# Gamepad_Seesaw_QT_rev_A.net
KiCad netlist of a schematic drawn in EAGLE
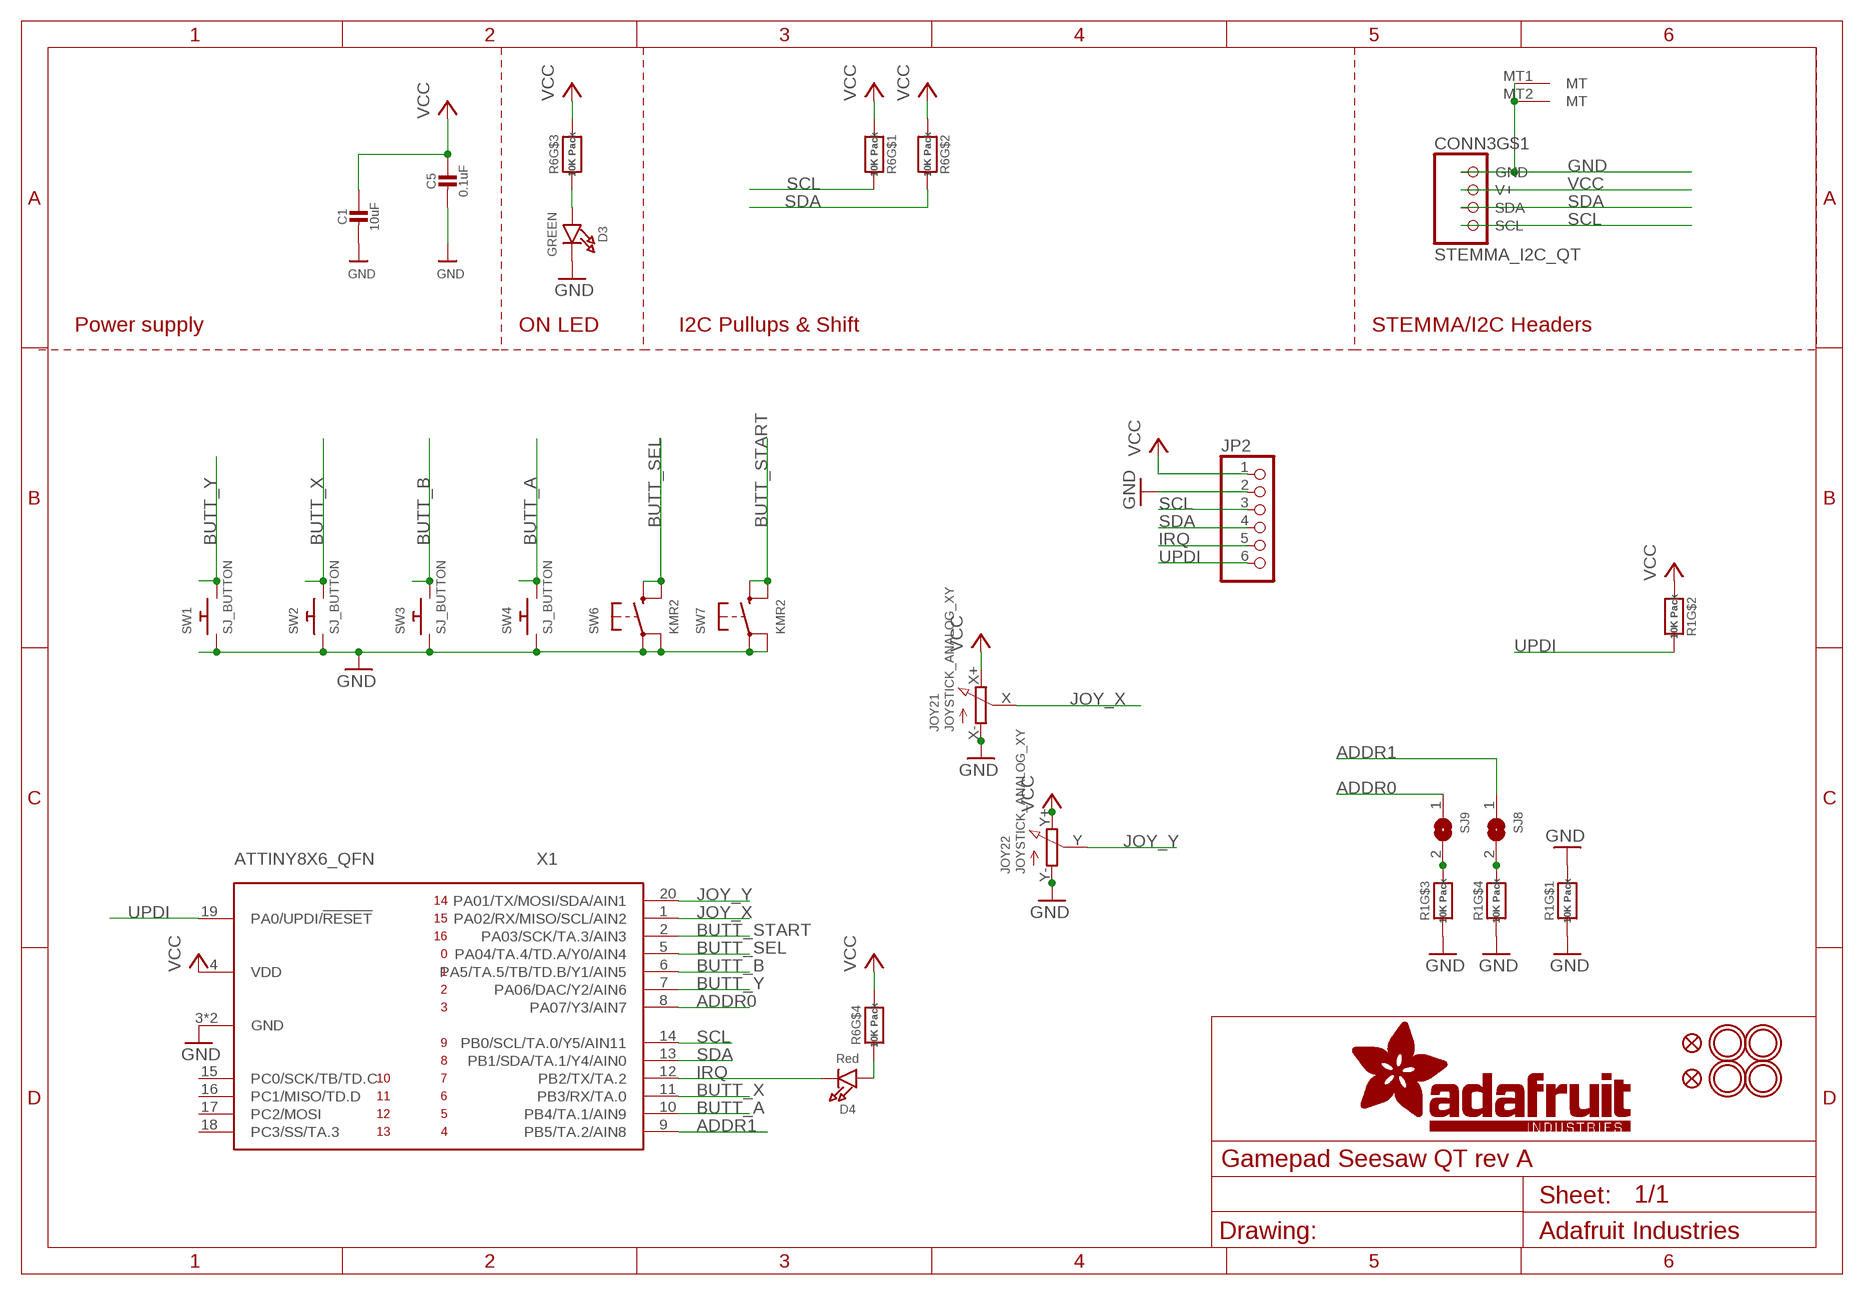
[diagram p0: schematic, sheet 1]

(export (version "E")
  (design (tool "Eeschema 10.0.6"))
  (components
    (comp (ref "C1")
      (value "10uF")
      (footprint "eagle-import:0805-NO")
      (libsource (lib "eagle-import") (part "CAP_CERAMIC0805-NOOUTLINE"))
    )
    (comp (ref "C5")
      (value "0.1uF")
      (footprint "eagle-import:0603-NO")
      (libsource (lib "eagle-import") (part "CAP_CERAMIC0603_NO"))
    )
    (comp (ref "CONN3")
      (value "STEMMA_I2C_QT")
      (footprint "eagle-import:JST_SH4")
      (libsource (lib "eagle-import") (part "STEMMA_I2C_QT"))
    )
    (comp (ref "D3")
      (value "GREEN")
      (footprint "eagle-import:CHIPLED_0603_NOOUTLINE")
      (libsource (lib "eagle-import") (part "LED0603_NOOUTLINE"))
    )
    (comp (ref "D4")
      (value "Red")
      (footprint "eagle-import:CHIPLED_0603_NOOUTLINE")
      (libsource (lib "eagle-import") (part "LED0603_NOOUTLINE"))
    )
    (comp (ref "FID1")
      (value "FIDUCIAL_1MM")
      (footprint "eagle-import:FIDUCIAL_1MM")
      (libsource (lib "eagle-import") (part "FIDUCIAL_1MM"))
    )
    (comp (ref "FID2")
      (value "FIDUCIAL_1MM")
      (footprint "eagle-import:FIDUCIAL_1MM")
      (libsource (lib "eagle-import") (part "FIDUCIAL_1MM"))
    )
    (comp (ref "JOY2")
      (value "JOYSTICK_ANALOG_XY")
      (footprint "eagle-import:JOYSTICK_ANALOG_MINITHM")
      (libsource (lib "eagle-import") (part "JOYSTICK_ANALOG_XY"))
    )
    (comp (ref "JP2")
      (value "HEADER-1X6ROUND")
      (footprint "eagle-import:1X06_ROUND")
      (libsource (lib "eagle-import") (part "HEADER-1X6ROUND"))
    )
    (comp (ref "R1")
      (value "10K Pack")
      (footprint "eagle-import:RESPACK_4X0603")
      (libsource (lib "eagle-import") (part "RESISTOR_4PACK"))
    )
    (comp (ref "R6")
      (value "10K Pack")
      (footprint "eagle-import:RESPACK_4X0603")
      (libsource (lib "eagle-import") (part "RESISTOR_4PACK"))
    )
    (comp (ref "SJ8")
      (value "SOLDERJUMPERCLOSED")
      (footprint "eagle-import:SOLDERJUMPER_CLOSEDWIRE")
      (libsource (lib "eagle-import") (part "SOLDERJUMPERCLOSED"))
    )
    (comp (ref "SJ9")
      (value "SOLDERJUMPERCLOSED")
      (footprint "eagle-import:SOLDERJUMPER_CLOSEDWIRE")
      (libsource (lib "eagle-import") (part "SOLDERJUMPERCLOSED"))
    )
    (comp (ref "SW1")
      (value "SJ_BUTTON")
      (footprint "eagle-import:PUSHBUTTON_SMD_SJ")
      (libsource (lib "eagle-import") (part "SWITCH_PUSHBUTTONSOFTTOUCHSMD_SJ"))
    )
    (comp (ref "SW2")
      (value "SJ_BUTTON")
      (footprint "eagle-import:PUSHBUTTON_SMD_SJ")
      (libsource (lib "eagle-import") (part "SWITCH_PUSHBUTTONSOFTTOUCHSMD_SJ"))
    )
    (comp (ref "SW3")
      (value "SJ_BUTTON")
      (footprint "eagle-import:PUSHBUTTON_SMD_SJ")
      (libsource (lib "eagle-import") (part "SWITCH_PUSHBUTTONSOFTTOUCHSMD_SJ"))
    )
    (comp (ref "SW4")
      (value "SJ_BUTTON")
      (footprint "eagle-import:PUSHBUTTON_SMD_SJ")
      (libsource (lib "eagle-import") (part "SWITCH_PUSHBUTTONSOFTTOUCHSMD_SJ"))
    )
    (comp (ref "SW6")
      (value "KMR2")
      (footprint "eagle-import:BTN_RKB2_4.6X2.8")
      (libsource (lib "eagle-import") (part "SWITCH_TACT_SMT_RKB2"))
    )
    (comp (ref "SW7")
      (value "KMR2")
      (footprint "eagle-import:BTN_RKB2_4.6X2.8")
      (libsource (lib "eagle-import") (part "SWITCH_TACT_SMT_RKB2"))
    )
    (comp (ref "U$1")
      (value "MOUNTINGHOLE2.5")
      (footprint "eagle-import:MOUNTINGHOLE_2.5_PLATED")
      (libsource (lib "eagle-import") (part "MOUNTINGHOLE2.5"))
    )
    (comp (ref "U$2")
      (value "MOUNTINGHOLE2.5")
      (footprint "eagle-import:MOUNTINGHOLE_2.5_PLATED")
      (libsource (lib "eagle-import") (part "MOUNTINGHOLE2.5"))
    )
    (comp (ref "U$3")
      (value "MOUNTINGHOLE2.5")
      (footprint "eagle-import:MOUNTINGHOLE_2.5_PLATED")
      (libsource (lib "eagle-import") (part "MOUNTINGHOLE2.5"))
    )
    (comp (ref "U$4")
      (value "MOUNTINGHOLE2.5")
      (footprint "eagle-import:MOUNTINGHOLE_2.5_PLATED")
      (libsource (lib "eagle-import") (part "MOUNTINGHOLE2.5"))
    )
    (comp (ref "X1")
      (value "ATTINY8X6_QFN")
      (footprint "eagle-import:QFN20_3MM")
      (libsource (lib "eagle-import") (part "ATTINY8X6_QFN"))
    )
  )
  (nets
    (net (code "1") (name "/ADDR0") (class "Default")
      (node (ref "SJ9") (pin "1") (pinfunction "1_1") (pintype "passive"))
      (node (ref "X1") (pin "8") (pinfunction "PA07/Y3/AIN7_8") (pintype "bidirectional"))
    )
    (net (code "2") (name "/ADDR1") (class "Default")
      (node (ref "SJ8") (pin "1") (pinfunction "1_1") (pintype "passive"))
      (node (ref "X1") (pin "9") (pinfunction "PB5/TA.2/AIN8_9") (pintype "bidirectional"))
    )
    (net (code "3") (name "/BUTT_A") (class "Default")
      (node (ref "SW4") (pin "P$2") (pinfunction "P$2_P$2") (pintype "passive"))
      (node (ref "X1") (pin "10") (pinfunction "PB4/TA.1/AIN9_10") (pintype "bidirectional"))
    )
    (net (code "4") (name "/BUTT_B") (class "Default")
      (node (ref "SW3") (pin "P$2") (pinfunction "P$2_P$2") (pintype "passive"))
      (node (ref "X1") (pin "6") (pinfunction "PA5/TA.5/TB/TD.B/Y1/AIN5_6") (pintype "bidirectional"))
    )
    (net (code "5") (name "/BUTT_SEL") (class "Default")
      (node (ref "SW6") (pin "B") (pinfunction "S_B") (pintype "passive"))
      (node (ref "SW6") (pin "B'") (pinfunction "S1_B'") (pintype "passive"))
      (node (ref "X1") (pin "5") (pinfunction "PA04/TA.4/TD.A/Y0/AIN4_5") (pintype "bidirectional"))
    )
    (net (code "6") (name "/BUTT_START") (class "Default")
      (node (ref "SW7") (pin "B") (pinfunction "S_B") (pintype "passive"))
      (node (ref "SW7") (pin "B'") (pinfunction "S1_B'") (pintype "passive"))
      (node (ref "X1") (pin "2") (pinfunction "PA03/SCK/TA.3/AIN3_2") (pintype "bidirectional"))
    )
    (net (code "7") (name "/BUTT_X") (class "Default")
      (node (ref "SW2") (pin "P$2") (pinfunction "P$2_P$2") (pintype "passive"))
      (node (ref "X1") (pin "11") (pinfunction "PB3/RX/TA.0_11") (pintype "bidirectional"))
    )
    (net (code "8") (name "/BUTT_Y") (class "Default")
      (node (ref "SW1") (pin "P$2") (pinfunction "P$2_P$2") (pintype "passive"))
      (node (ref "X1") (pin "7") (pinfunction "PA06/DAC/Y2/AIN6_7") (pintype "bidirectional"))
    )
    (net (code "9") (name "/IRQ") (class "Default")
      (node (ref "D4") (pin "C") (pinfunction "C_C") (pintype "passive"))
      (node (ref "JP2") (pin "5") (pinfunction "5_5") (pintype "passive"))
      (node (ref "X1") (pin "12") (pinfunction "PB2/TX/TA.2_12") (pintype "bidirectional"))
    )
    (net (code "10") (name "/JOY_X") (class "Default")
      (node (ref "JOY2") (pin "X") (pinfunction "S_X") (pintype "passive"))
      (node (ref "X1") (pin "1") (pinfunction "PA02/RX/MISO/SCL/AIN2_1") (pintype "bidirectional"))
    )
    (net (code "11") (name "/JOY_Y") (class "Default")
      (node (ref "JOY2") (pin "Y") (pinfunction "S_Y") (pintype "passive"))
      (node (ref "X1") (pin "20") (pinfunction "PA01/TX/MOSI/SDA/AIN1_20") (pintype "bidirectional"))
    )
    (net (code "12") (name "/SCL") (class "Default")
      (node (ref "CONN3") (pin "4") (pinfunction "SCL_4") (pintype "passive"))
      (node (ref "JP2") (pin "3") (pinfunction "3_3") (pintype "passive"))
      (node (ref "R6") (pin "8") (pinfunction "2_8") (pintype "passive"))
      (node (ref "X1") (pin "14") (pinfunction "PB0/SCL/TA.0/Y5/AIN11_14") (pintype "bidirectional"))
    )
    (net (code "13") (name "/SDA") (class "Default")
      (node (ref "CONN3") (pin "3") (pinfunction "SDA_3") (pintype "passive"))
      (node (ref "JP2") (pin "4") (pinfunction "4_4") (pintype "passive"))
      (node (ref "R6") (pin "7") (pinfunction "2_7") (pintype "passive"))
      (node (ref "X1") (pin "13") (pinfunction "PB1/SDA/TA.1/Y4/AIN0_13") (pintype "bidirectional"))
    )
    (net (code "14") (name "/UPDI") (class "Default")
      (node (ref "JP2") (pin "6") (pinfunction "6_6") (pintype "passive"))
      (node (ref "R1") (pin "7") (pinfunction "2_7") (pintype "passive"))
      (node (ref "X1") (pin "19") (pinfunction "PA0/UPDI/~{RESET}_19") (pintype "bidirectional"))
    )
    (net (code "15") (name "GND") (class "Default")
      (node (ref "C1") (pin "2") (pinfunction "2_2") (pintype "passive"))
      (node (ref "C5") (pin "2") (pinfunction "2_2") (pintype "passive"))
      (node (ref "CONN3") (pin "1") (pinfunction "GND_1") (pintype "passive"))
      (node (ref "CONN3") (pin "MT1") (pinfunction "MT_MT1") (pintype "bidirectional"))
      (node (ref "CONN3") (pin "MT2") (pinfunction "MT_MT2") (pintype "bidirectional"))
      (node (ref "D3") (pin "C") (pinfunction "C_C") (pintype "passive"))
      (node (ref "JOY2") (pin "X-") (pinfunction "A_X-") (pintype "passive"))
      (node (ref "JOY2") (pin "Y-") (pinfunction "A_Y-") (pintype "passive"))
      (node (ref "JP2") (pin "2") (pinfunction "2_2") (pintype "passive"))
      (node (ref "R1") (pin "1") (pinfunction "1_1") (pintype "passive"))
      (node (ref "R1") (pin "3") (pinfunction "1_3") (pintype "passive"))
      (node (ref "R1") (pin "4") (pinfunction "1_4") (pintype "passive"))
      (node (ref "R1") (pin "8") (pinfunction "2_8") (pintype "passive"))
      (node (ref "SW1") (pin "P$1") (pinfunction "P$1_P$1") (pintype "passive"))
      (node (ref "SW2") (pin "P$1") (pinfunction "P$1_P$1") (pintype "passive"))
      (node (ref "SW3") (pin "P$1") (pinfunction "P$1_P$1") (pintype "passive"))
      (node (ref "SW4") (pin "P$1") (pinfunction "P$1_P$1") (pintype "passive"))
      (node (ref "SW6") (pin "A") (pinfunction "P_A") (pintype "passive"))
      (node (ref "SW6") (pin "A'") (pinfunction "P1_A'") (pintype "passive"))
      (node (ref "SW7") (pin "A") (pinfunction "P_A") (pintype "passive"))
      (node (ref "SW7") (pin "A'") (pinfunction "P1_A'") (pintype "passive"))
      (node (ref "X1") (pin "3") (pinfunction "GND_3") (pintype "power_in"))
      (node (ref "X1") (pin "PAD") (pinfunction "GND_PAD") (pintype "power_in"))
    )
    (net (code "16") (name "Net-(R1C-2)") (class "Default")
      (node (ref "R1") (pin "6") (pinfunction "2_6") (pintype "passive"))
      (node (ref "SJ9") (pin "2") (pinfunction "2_2") (pintype "passive"))
    )
    (net (code "17") (name "Net-(R1D-2)") (class "Default")
      (node (ref "R1") (pin "5") (pinfunction "2_5") (pintype "passive"))
      (node (ref "SJ8") (pin "2") (pinfunction "2_2") (pintype "passive"))
    )
    (net (code "18") (name "Net-(R6C-1)") (class "Default")
      (node (ref "D3") (pin "A") (pinfunction "A_A") (pintype "passive"))
      (node (ref "R6") (pin "3") (pinfunction "1_3") (pintype "passive"))
    )
    (net (code "19") (name "Net-(R6D-1)") (class "Default")
      (node (ref "D4") (pin "A") (pinfunction "A_A") (pintype "passive"))
      (node (ref "R6") (pin "4") (pinfunction "1_4") (pintype "passive"))
    )
    (net (code "20") (name "VCC") (class "Default")
      (node (ref "C1") (pin "1") (pinfunction "1_1") (pintype "passive"))
      (node (ref "C5") (pin "1") (pinfunction "1_1") (pintype "passive"))
      (node (ref "CONN3") (pin "2") (pinfunction "V+_2") (pintype "passive"))
      (node (ref "JOY2") (pin "X+") (pinfunction "E_X+") (pintype "passive"))
      (node (ref "JOY2") (pin "Y+") (pinfunction "E_Y+") (pintype "passive"))
      (node (ref "JP2") (pin "1") (pinfunction "1_1") (pintype "passive"))
      (node (ref "R1") (pin "2") (pinfunction "1_2") (pintype "passive"))
      (node (ref "R6") (pin "1") (pinfunction "1_1") (pintype "passive"))
      (node (ref "R6") (pin "2") (pinfunction "1_2") (pintype "passive"))
      (node (ref "R6") (pin "5") (pinfunction "2_5") (pintype "passive"))
      (node (ref "R6") (pin "6") (pinfunction "2_6") (pintype "passive"))
      (node (ref "X1") (pin "4") (pinfunction "VDD_4") (pintype "power_in"))
    )
    (net (code "21") (name "unconnected-(X1-PC0{slash}SCK{slash}TB{slash}TD.C-Pad15)") (class "Default")
      (node (ref "X1") (pin "15") (pinfunction "PC0/SCK/TB/TD.C_15") (pintype "bidirectional"))
    )
    (net (code "22") (name "unconnected-(X1-PC1{slash}MISO{slash}TD.D-Pad16)") (class "Default")
      (node (ref "X1") (pin "16") (pinfunction "PC1/MISO/TD.D_16") (pintype "bidirectional"))
    )
    (net (code "23") (name "unconnected-(X1-PC2{slash}MOSI-Pad17)") (class "Default")
      (node (ref "X1") (pin "17") (pinfunction "PC2/MOSI_17") (pintype "bidirectional"))
    )
    (net (code "24") (name "unconnected-(X1-PC3{slash}SS{slash}TA.3-Pad18)") (class "Default")
      (node (ref "X1") (pin "18") (pinfunction "PC3/SS/TA.3_18") (pintype "bidirectional"))
    )
  )
)
